# tree.net
KiCad netlist of a schematic drawn in EAGLE
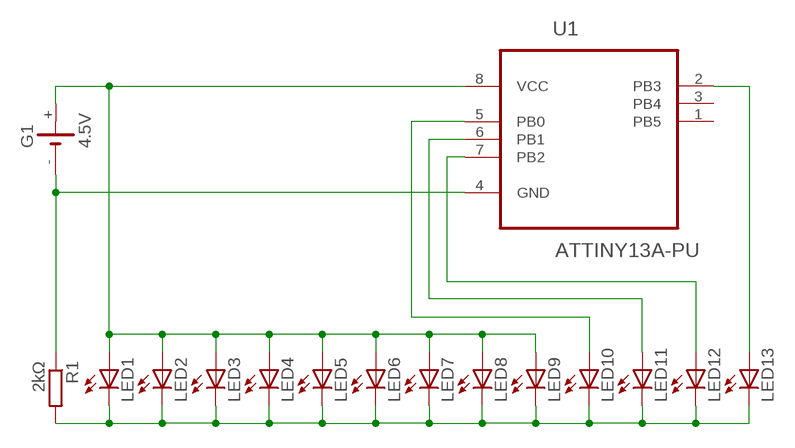
[diagram p0: schematic, sheet 1]

(export (version "E")
  (design (tool "Eeschema 10.0.6"))
  (components
    (comp (ref "G1")
      (value "4.5V")
      (footprint "eagle-import:CH291-1220LF")
      (libsource (lib "eagle-import") (part "CH291-1220LF"))
    )
    (comp (ref "LED1")
      (value "LED3MM")
      (footprint "eagle-import:LED3MM")
      (libsource (lib "eagle-import") (part "LED3MM"))
    )
    (comp (ref "LED2")
      (value "LED3MM")
      (footprint "eagle-import:LED3MM")
      (libsource (lib "eagle-import") (part "LED3MM"))
    )
    (comp (ref "LED3")
      (value "LED3MM")
      (footprint "eagle-import:LED3MM")
      (libsource (lib "eagle-import") (part "LED3MM"))
    )
    (comp (ref "LED4")
      (value "LED3MM")
      (footprint "eagle-import:LED3MM")
      (libsource (lib "eagle-import") (part "LED3MM"))
    )
    (comp (ref "LED5")
      (value "LED3MM")
      (footprint "eagle-import:LED3MM")
      (libsource (lib "eagle-import") (part "LED3MM"))
    )
    (comp (ref "LED6")
      (value "LED3MM")
      (footprint "eagle-import:LED3MM")
      (libsource (lib "eagle-import") (part "LED3MM"))
    )
    (comp (ref "LED7")
      (value "LED3MM")
      (footprint "eagle-import:LED3MM")
      (libsource (lib "eagle-import") (part "LED3MM"))
    )
    (comp (ref "LED8")
      (value "LED3MM")
      (footprint "eagle-import:LED3MM")
      (libsource (lib "eagle-import") (part "LED3MM"))
    )
    (comp (ref "LED9")
      (value "LED3MM")
      (footprint "eagle-import:LED3MM")
      (libsource (lib "eagle-import") (part "LED3MM"))
    )
    (comp (ref "LED10")
      (value "LED3MM")
      (footprint "eagle-import:LED3MM")
      (libsource (lib "eagle-import") (part "LED3MM"))
    )
    (comp (ref "LED11")
      (value "LED3MM")
      (footprint "eagle-import:LED3MM")
      (libsource (lib "eagle-import") (part "LED3MM"))
    )
    (comp (ref "LED12")
      (value "LED3MM")
      (footprint "eagle-import:LED3MM")
      (libsource (lib "eagle-import") (part "LED3MM"))
    )
    (comp (ref "LED13")
      (value "LED3MM")
      (footprint "eagle-import:LED3MM")
      (libsource (lib "eagle-import") (part "LED3MM"))
    )
    (comp (ref "R1")
      (value "2kΩ")
      (footprint "eagle-import:0204_5")
      (libsource (lib "eagle-import") (part "R-EU_0204/5"))
    )
    (comp (ref "U1")
      (value "ATTINY13A-PU")
      (footprint "eagle-import:DIP254P762X533-8")
      (libsource (lib "eagle-import") (part "ATTINY13A-PU"))
    )
  )
  (nets
    (net (code "1") (name "Net-(LED1-C)") (class "Default")
      (node (ref "LED1") (pin "K") (pinfunction "C_K") (pintype "passive"))
      (node (ref "LED10") (pin "K") (pinfunction "C_K") (pintype "passive"))
      (node (ref "LED11") (pin "K") (pinfunction "C_K") (pintype "passive"))
      (node (ref "LED12") (pin "K") (pinfunction "C_K") (pintype "passive"))
      (node (ref "LED13") (pin "K") (pinfunction "C_K") (pintype "passive"))
      (node (ref "LED2") (pin "K") (pinfunction "C_K") (pintype "passive"))
      (node (ref "LED3") (pin "K") (pinfunction "C_K") (pintype "passive"))
      (node (ref "LED4") (pin "K") (pinfunction "C_K") (pintype "passive"))
      (node (ref "LED5") (pin "K") (pinfunction "C_K") (pintype "passive"))
      (node (ref "LED6") (pin "K") (pinfunction "C_K") (pintype "passive"))
      (node (ref "LED7") (pin "K") (pinfunction "C_K") (pintype "passive"))
      (node (ref "LED8") (pin "K") (pinfunction "C_K") (pintype "passive"))
      (node (ref "LED9") (pin "K") (pinfunction "C_K") (pintype "passive"))
      (node (ref "R1") (pin "2") (pinfunction "2_2") (pintype "passive"))
    )
    (net (code "2") (name "Net-(U1-GND)") (class "Default")
      (node (ref "G1") (pin "-") (pinfunction "-_-") (pintype "passive"))
      (node (ref "R1") (pin "1") (pinfunction "1_1") (pintype "passive"))
      (node (ref "U1") (pin "4") (pinfunction "GND_4") (pintype "passive"))
    )
    (net (code "3") (name "Net-(U1-PB0)") (class "Default")
      (node (ref "LED10") (pin "A") (pinfunction "A_A") (pintype "passive"))
      (node (ref "U1") (pin "5") (pinfunction "PB0_5") (pintype "bidirectional"))
    )
    (net (code "4") (name "Net-(U1-PB1)") (class "Default")
      (node (ref "LED11") (pin "A") (pinfunction "A_A") (pintype "passive"))
      (node (ref "U1") (pin "6") (pinfunction "PB1_6") (pintype "bidirectional"))
    )
    (net (code "5") (name "Net-(U1-PB2)") (class "Default")
      (node (ref "LED12") (pin "A") (pinfunction "A_A") (pintype "passive"))
      (node (ref "U1") (pin "7") (pinfunction "PB2_7") (pintype "bidirectional"))
    )
    (net (code "6") (name "Net-(U1-PB3)") (class "Default")
      (node (ref "LED13") (pin "A") (pinfunction "A_A") (pintype "passive"))
      (node (ref "U1") (pin "2") (pinfunction "PB3_2") (pintype "bidirectional"))
    )
    (net (code "7") (name "Net-(U1-VCC)") (class "Default")
      (node (ref "G1") (pin "+") (pinfunction "+_+") (pintype "passive"))
      (node (ref "LED1") (pin "A") (pinfunction "A_A") (pintype "passive"))
      (node (ref "LED2") (pin "A") (pinfunction "A_A") (pintype "passive"))
      (node (ref "LED3") (pin "A") (pinfunction "A_A") (pintype "passive"))
      (node (ref "LED4") (pin "A") (pinfunction "A_A") (pintype "passive"))
      (node (ref "LED5") (pin "A") (pinfunction "A_A") (pintype "passive"))
      (node (ref "LED6") (pin "A") (pinfunction "A_A") (pintype "passive"))
      (node (ref "LED7") (pin "A") (pinfunction "A_A") (pintype "passive"))
      (node (ref "LED8") (pin "A") (pinfunction "A_A") (pintype "passive"))
      (node (ref "LED9") (pin "A") (pinfunction "A_A") (pintype "passive"))
      (node (ref "U1") (pin "8") (pinfunction "VCC_8") (pintype "power_in"))
    )
    (net (code "8") (name "unconnected-(U1-PB4-Pad3)") (class "Default")
      (node (ref "U1") (pin "3") (pinfunction "PB4_3") (pintype "bidirectional"))
    )
    (net (code "9") (name "unconnected-(U1-PB5-Pad1)") (class "Default")
      (node (ref "U1") (pin "1") (pinfunction "PB5_1") (pintype "bidirectional"))
    )
  )
)
